# olmRTCbreakout.net
KiCad netlist of a schematic drawn in EAGLE
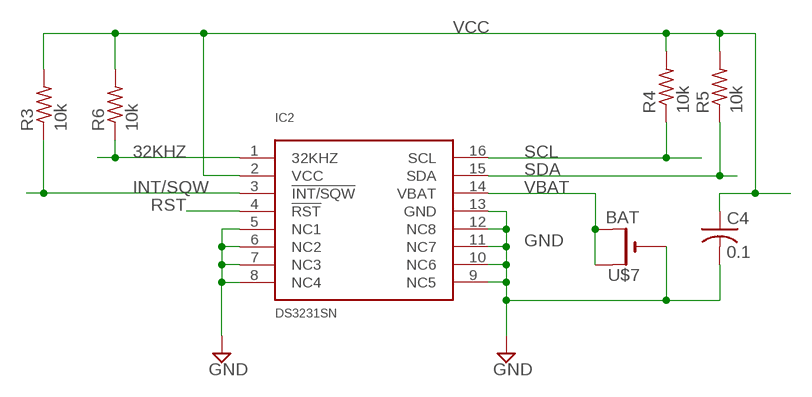
[diagram p0: schematic, sheet 1]

(export (version "E")
  (design (tool "Eeschema 10.0.6"))
  (components
    (comp (ref "C4")
      (value "0.1")
      (footprint "eagle-import:C0805K")
      (libsource (lib "eagle-import") (part "C-USC0805K"))
    )
    (comp (ref "IC2")
      (value "DS3231SN")
      (footprint "eagle-import:SO16W")
      (libsource (lib "eagle-import") (part "DS3231SN"))
    )
    (comp (ref "R3")
      (value "10k")
      (footprint "eagle-import:R0805")
      (libsource (lib "eagle-import") (part "R-US_R0805"))
    )
    (comp (ref "R4")
      (value "10k")
      (footprint "eagle-import:R0805")
      (libsource (lib "eagle-import") (part "R-US_R0805"))
    )
    (comp (ref "R5")
      (value "10k")
      (footprint "eagle-import:R0805")
      (libsource (lib "eagle-import") (part "R-US_R0805"))
    )
    (comp (ref "R6")
      (value "10k")
      (footprint "eagle-import:R0805")
      (libsource (lib "eagle-import") (part "R-US_R0805"))
    )
    (comp (ref "U$7")
      (value "BAT")
      (footprint "eagle-import:CR1220-SMD")
      (libsource (lib "eagle-import") (part "CR1220SMT"))
    )
  )
  (nets
    (net (code "1") (name "/32KHZ") (class "Default")
      (node (ref "IC2") (pin "1") (pinfunction "32KHZ_1") (pintype "bidirectional"))
      (node (ref "R6") (pin "1") (pinfunction "1_1") (pintype "passive"))
    )
    (net (code "2") (name "/INT{slash}SQW") (class "Default")
      (node (ref "IC2") (pin "3") (pinfunction "~{INT/SQW}_3") (pintype "bidirectional"))
      (node (ref "R3") (pin "1") (pinfunction "1_1") (pintype "passive"))
    )
    (net (code "3") (name "/RST") (class "Default")
      (node (ref "IC2") (pin "4") (pinfunction "~{RST}_4") (pintype "bidirectional"))
    )
    (net (code "4") (name "/SCL") (class "Default")
      (node (ref "IC2") (pin "16") (pinfunction "SCL_16") (pintype "bidirectional"))
      (node (ref "R4") (pin "1") (pinfunction "1_1") (pintype "passive"))
    )
    (net (code "5") (name "/SDA") (class "Default")
      (node (ref "IC2") (pin "15") (pinfunction "SDA_15") (pintype "bidirectional"))
      (node (ref "R5") (pin "1") (pinfunction "1_1") (pintype "passive"))
    )
    (net (code "6") (name "/VBAT") (class "Default")
      (node (ref "IC2") (pin "14") (pinfunction "VBAT_14") (pintype "bidirectional"))
      (node (ref "U$7") (pin "+$1") (pinfunction "+_+$1") (pintype "passive"))
      (node (ref "U$7") (pin "+$2") (pinfunction "+1_+$2") (pintype "passive"))
    )
    (net (code "7") (name "/VCC") (class "Default")
      (node (ref "C4") (pin "1") (pinfunction "1_1") (pintype "passive"))
      (node (ref "IC2") (pin "2") (pinfunction "VCC_2") (pintype "bidirectional"))
      (node (ref "R3") (pin "2") (pinfunction "2_2") (pintype "passive"))
      (node (ref "R4") (pin "2") (pinfunction "2_2") (pintype "passive"))
      (node (ref "R5") (pin "2") (pinfunction "2_2") (pintype "passive"))
      (node (ref "R6") (pin "2") (pinfunction "2_2") (pintype "passive"))
    )
    (net (code "8") (name "GND") (class "Default")
      (node (ref "C4") (pin "2") (pinfunction "2_2") (pintype "passive"))
      (node (ref "IC2") (pin "10") (pinfunction "NC6_10") (pintype "bidirectional"))
      (node (ref "IC2") (pin "11") (pinfunction "NC7_11") (pintype "bidirectional"))
      (node (ref "IC2") (pin "12") (pinfunction "NC8_12") (pintype "bidirectional"))
      (node (ref "IC2") (pin "13") (pinfunction "GND_13") (pintype "bidirectional"))
      (node (ref "IC2") (pin "5") (pinfunction "NC1_5") (pintype "bidirectional"))
      (node (ref "IC2") (pin "6") (pinfunction "NC2_6") (pintype "bidirectional"))
      (node (ref "IC2") (pin "7") (pinfunction "NC3_7") (pintype "bidirectional"))
      (node (ref "IC2") (pin "8") (pinfunction "NC4_8") (pintype "bidirectional"))
      (node (ref "IC2") (pin "9") (pinfunction "NC5_9") (pintype "bidirectional"))
      (node (ref "U$7") (pin "-") (pinfunction "-_-") (pintype "passive"))
    )
  )
)
